# efr32_ioport.net
KiCad netlist of a schematic drawn in Altium Designer
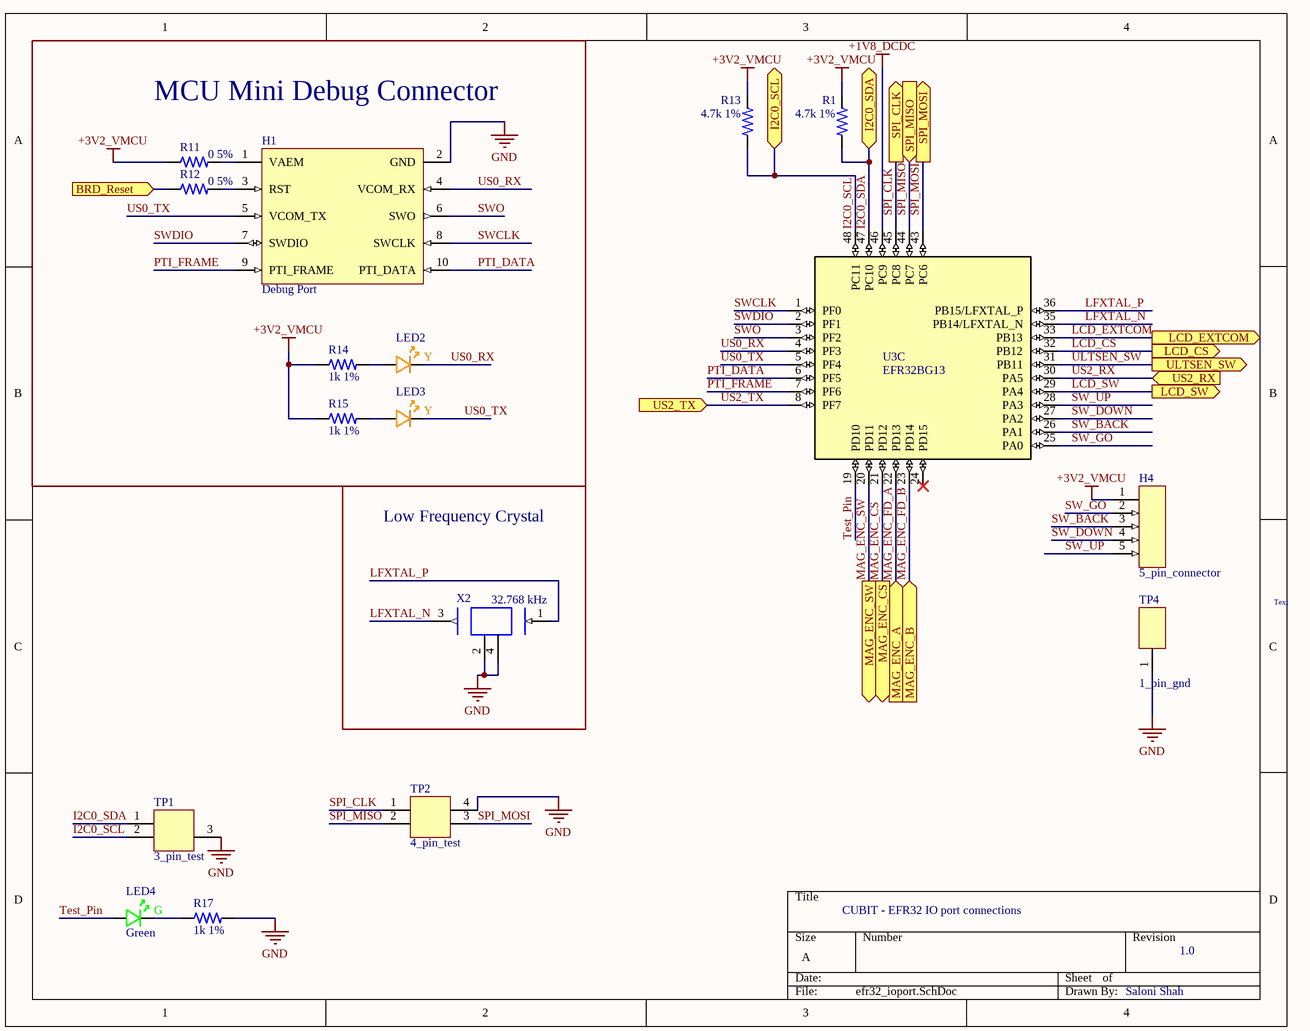
[diagram p0: efr32_ioport.SchDoc]

(export (version "E")
  (design (tool "Eeschema 10.0.6"))
  (components
    (comp (ref "H1")
      (value "Debug Port")
      (footprint "Amphenol_20021121_0")
      (description "CONN HEADER SMD 10POS 1.27MM. Connector Header Surface Mount 10 position 0.050\"")
      (fields
        (field (name "MANUFACTURER") "Amphenol ICC / FCI")
        (field (name "MANUFACTURER PART NUMBER") "20021121-00010C1LF")
      )
      (libsource (lib "LPEDT_proj_lib") (part "20021121-00010C1LF"))
    )
    (comp (ref "H4")
      (value "5_pin_connector")
      (footprint "5_PIN_100MIL")
      (libsource (lib "LPEDT_proj_lib") (part "5_pin_connector"))
    )
    (comp (ref "LED2")
      (value "150060YS75000")
      (footprint "LED_0603_RED_WL-SMCW")
      (description "Led, Yellow, 590 Nm, 2 V, 30 Ma, 120 Mcd Rohs Compliant: Yes")
      (fields (field (name "MANUFACTURER") "Wurth Electronics"))
      (libsource (lib "LPEDT_proj_lib") (part "150060YS75000"))
    )
    (comp (ref "LED3")
      (value "150060YS75000")
      (footprint "LED_0603_RED_WL-SMCW")
      (description "Led, Yellow, 590 Nm, 2 V, 30 Ma, 120 Mcd Rohs Compliant: Yes")
      (fields (field (name "MANUFACTURER") "Wurth Electronics"))
      (libsource (lib "LPEDT_proj_lib") (part "150060YS75000"))
    )
    (comp (ref "LED4")
      (value "Green")
      (footprint "LED_0603_RED_WL-SMCW")
      (description "Led Green Clear 0603 SMD")
      (fields
        (field (name "MANUFACTURER") "QT-Brightek")
        (field (name "MANUFACTURER PART NUMBER") "QBLP601-AG1")
      )
      (libsource (lib "LPEDT_proj_lib") (part "QBLP601-AG1"))
    )
    (comp (ref "R1")
      (value "4.7k 1%")
      (footprint "LPEDT_proj_lib:CAP_0603_1MM")
      (description "Res Thick Film 0603 4.7K Ohm 1% 1/10W ±100ppm/°C Molded SMD Paper T/R")
      (fields
        (field (name "MANUFACTURER") "Yageo")
        (field (name "MANUFACTURER PART NUMBER") "AF0603FR-074K7L")
      )
      (libsource (lib "LPEDT_proj_lib") (part "AF0603FR-074K7L"))
    )
    (comp (ref "R11")
      (value "0 5%")
      (footprint "CAP_0402_1mm")
      (description "Res 0 Ohms ±5% 0.063 W 0402 Thick Film Surface Mount Chip Resistor")
      (fields
        (field (name "MANUFACTURER") "Samsung")
        (field (name "MANUFACTURER PART NUMBER") "RC1005J000CS")
      )
      (libsource (lib "LPEDT_proj_lib") (part "RC1005J000CS"))
    )
    (comp (ref "R12")
      (value "0 5%")
      (footprint "CAP_0402_1mm")
      (description "Res 0 Ohms ±5% 0.063 W 0402 Thick Film Surface Mount Chip Resistor")
      (fields
        (field (name "MANUFACTURER") "Samsung")
        (field (name "MANUFACTURER PART NUMBER") "RC1005J000CS")
      )
      (libsource (lib "LPEDT_proj_lib") (part "RC1005J000CS"))
    )
    (comp (ref "R13")
      (value "4.7k 1%")
      (footprint "LPEDT_proj_lib:CAP_0603_1MM")
      (description "Res Thick Film 0603 4.7K Ohm 1% 1/10W ±100ppm/°C Molded SMD Paper T/R")
      (fields
        (field (name "MANUFACTURER") "Yageo")
        (field (name "MANUFACTURER PART NUMBER") "AF0603FR-074K7L")
      )
      (libsource (lib "LPEDT_proj_lib") (part "AF0603FR-074K7L"))
    )
    (comp (ref "R14")
      (value "1k 1%")
      (footprint "2_Chip_0603_RMCF")
      (description "Res 1K Ohm 1% 0.1W(1/10W) ±100ppm/C Pad SMD Automotive T/R")
      (fields
        (field (name "MANUFACTURER") "Stackpole Electronics")
        (field (name "MANUFACTURER PART NUMBER") "RMCF0603FT1K00")
      )
      (libsource (lib "LPEDT_proj_lib") (part "RMCF0603FT1K00"))
    )
    (comp (ref "R15")
      (value "1k 1%")
      (footprint "2_Chip_0603_RMCF")
      (description "Res 1K Ohm 1% 0.1W(1/10W) ±100ppm/C Pad SMD Automotive T/R")
      (fields
        (field (name "MANUFACTURER") "Stackpole Electronics")
        (field (name "MANUFACTURER PART NUMBER") "RMCF0603FT1K00")
      )
      (libsource (lib "LPEDT_proj_lib") (part "RMCF0603FT1K00"))
    )
    (comp (ref "R17")
      (value "1k 1%")
      (footprint "2_Chip_0603_RMCF")
      (description "Res 1K Ohm 1% 0.1W(1/10W) ±100ppm/C Pad SMD Automotive T/R")
      (fields
        (field (name "MANUFACTURER") "Stackpole Electronics")
        (field (name "MANUFACTURER PART NUMBER") "RMCF0603FT1K00")
      )
      (libsource (lib "LPEDT_proj_lib") (part "RMCF0603FT1K00"))
    )
    (comp (ref "TP1")
      (value "3_pin_test")
      (footprint "3_PIN_100mil")
      (libsource (lib "LPEDT_proj_lib") (part "3_pin_test"))
    )
    (comp (ref "TP2")
      (value "4_pin_test")
      (footprint "4_PIN_100MIL")
      (libsource (lib "LPEDT_proj_lib") (part "4_pin_test"))
    )
    (comp (ref "TP4")
      (value "1_pin_gnd")
      (footprint "1_PIN_100MIL")
      (libsource (lib "LPEDT_proj_lib") (part "1_pin_gnd"))
    )
    (comp (ref "U3")
      (value "EFR32BG13")
      (footprint "48-QFN_7x7")
      (description "Blue Gecko QFN48 2.4 G 19 dB BLE/Proprietary 512 kB 64 kB(RAM) 31GPIO")
      (fields
        (field (name "MANUFACTURER") "Silicon Labs")
        (field (name "MANUFACTURER PART NUMBER") "EFR32BG13P732F512GM48-D")
      )
      (libsource (lib "LPEDT_proj_lib") (part "EFR32BG13P732F512GM48-D"))
    )
    (comp (ref "X2")
      (value "32.768 kHz")
      (footprint "OSC_ASDDV-48.000MHZ-LC-T")
      (description "Oscillator XO 0.032768MHz ±25ppm 15pF CMOS 60% 1.8V 4-Pin SMD T/R")
      (fields
        (field (name "MANUFACTURER") "Abracon")
        (field (name "MANUFACTURER PART NUMBER") "ASDK2-32.768KHZ-LR-T3")
      )
      (libsource (lib "LPEDT_proj_lib") (part "ASDK2-32.768KHZ-LR-T3"))
    )
  )
  (nets
    (net (code "1") (name "+1V8_DCDC") (class "Default")
      (node (ref "U3") (pin "46") (pinfunction "PC9_46") (pintype "bidirectional"))
    )
    (net (code "2") (name "+3V2_VMCU") (class "Default")
      (node (ref "H4") (pin "1") (pintype "power_in"))
      (node (ref "R1") (pin "1") (pinfunction "1_1") (pintype "passive"))
      (node (ref "R11") (pin "1") (pinfunction "1_1") (pintype "passive"))
      (node (ref "R13") (pin "1") (pinfunction "1_1") (pintype "passive"))
      (node (ref "R14") (pin "1") (pinfunction "1_1") (pintype "passive"))
      (node (ref "R15") (pin "1") (pinfunction "1_1") (pintype "passive"))
    )
    (net (code "3") (name "/BRD_Reset") (class "Default")
      (node (ref "R12") (pin "1") (pinfunction "1_1") (pintype "passive"))
    )
    (net (code "4") (name "/I2C0_SCL") (class "Default")
      (node (ref "R13") (pin "2") (pinfunction "2_2") (pintype "passive"))
      (node (ref "TP1") (pin "2") (pintype "passive"))
      (node (ref "U3") (pin "48") (pinfunction "PC11_48") (pintype "bidirectional"))
    )
    (net (code "5") (name "/I2C0_SDA") (class "Default")
      (node (ref "R1") (pin "2") (pinfunction "2_2") (pintype "passive"))
      (node (ref "TP1") (pin "1") (pintype "passive"))
      (node (ref "U3") (pin "47") (pinfunction "PC10_47") (pintype "bidirectional"))
    )
    (net (code "6") (name "/LCD_CS") (class "Default")
      (node (ref "U3") (pin "32") (pinfunction "PB12_32") (pintype "bidirectional"))
    )
    (net (code "7") (name "/LCD_EXTCOM") (class "Default")
      (node (ref "U3") (pin "33") (pinfunction "PB13_33") (pintype "bidirectional"))
    )
    (net (code "8") (name "/LCD_SW") (class "Default")
      (node (ref "U3") (pin "29") (pinfunction "PA4_29") (pintype "bidirectional"))
    )
    (net (code "9") (name "/LFXTAL_N") (class "Default")
      (node (ref "U3") (pin "35") (pinfunction "PB14/LFXTAL_N_35") (pintype "bidirectional"))
      (node (ref "X2") (pin "3") (pintype "output"))
    )
    (net (code "10") (name "/LFXTAL_P") (class "Default")
      (node (ref "U3") (pin "36") (pinfunction "PB15/LFXTAL_P_36") (pintype "bidirectional"))
      (node (ref "X2") (pin "1") (pintype "input"))
    )
    (net (code "11") (name "/MAG_ENC_CS") (class "Default")
      (node (ref "U3") (pin "21") (pinfunction "PD12_21") (pintype "bidirectional"))
    )
    (net (code "12") (name "/MAG_ENC_FD_A") (class "Default")
      (node (ref "U3") (pin "22") (pinfunction "PD13_22") (pintype "bidirectional"))
    )
    (net (code "13") (name "/MAG_ENC_FD_B") (class "Default")
      (node (ref "U3") (pin "23") (pinfunction "PD14_23") (pintype "bidirectional"))
    )
    (net (code "14") (name "/MAG_ENC_SW") (class "Default")
      (node (ref "U3") (pin "20") (pinfunction "PD11_20") (pintype "bidirectional"))
    )
    (net (code "15") (name "/PTI_DATA") (class "Default")
      (node (ref "H1") (pin "10") (pinfunction "PTI_DATA_10") (pintype "input"))
      (node (ref "U3") (pin "6") (pinfunction "PF5_6") (pintype "bidirectional"))
    )
    (net (code "16") (name "/PTI_FRAME") (class "Default")
      (node (ref "H1") (pin "9") (pinfunction "PTI_FRAME_9") (pintype "input"))
      (node (ref "U3") (pin "7") (pinfunction "PF6_7") (pintype "bidirectional"))
    )
    (net (code "17") (name "/SPI_CLK") (class "Default")
      (node (ref "TP2") (pin "1") (pintype "passive"))
      (node (ref "U3") (pin "45") (pinfunction "PC8_45") (pintype "bidirectional"))
    )
    (net (code "18") (name "/SPI_MISO") (class "Default")
      (node (ref "TP2") (pin "2") (pintype "passive"))
      (node (ref "U3") (pin "44") (pinfunction "PC7_44") (pintype "bidirectional"))
    )
    (net (code "19") (name "/SPI_MOSI") (class "Default")
      (node (ref "TP2") (pin "3") (pintype "passive"))
      (node (ref "U3") (pin "43") (pinfunction "PC6_43") (pintype "bidirectional"))
    )
    (net (code "20") (name "/SWCLK") (class "Default")
      (node (ref "H1") (pin "8") (pinfunction "SWCLK_8") (pintype "input"))
      (node (ref "U3") (pin "1") (pinfunction "PF0_1") (pintype "bidirectional"))
    )
    (net (code "21") (name "/SWDIO") (class "Default")
      (node (ref "H1") (pin "7") (pinfunction "SWDIO_7") (pintype "bidirectional"))
      (node (ref "U3") (pin "2") (pinfunction "PF1_2") (pintype "bidirectional"))
    )
    (net (code "22") (name "/SWO") (class "Default")
      (node (ref "H1") (pin "6") (pinfunction "SWO_6") (pintype "output"))
      (node (ref "U3") (pin "3") (pinfunction "PF2_3") (pintype "bidirectional"))
    )
    (net (code "23") (name "/SW_BACK") (class "Default")
      (node (ref "H4") (pin "3") (pintype "input"))
      (node (ref "U3") (pin "26") (pinfunction "PA1_26") (pintype "bidirectional"))
    )
    (net (code "24") (name "/SW_DOWN") (class "Default")
      (node (ref "H4") (pin "4") (pintype "input"))
      (node (ref "U3") (pin "27") (pinfunction "PA2_27") (pintype "bidirectional"))
    )
    (net (code "25") (name "/SW_GO") (class "Default")
      (node (ref "H4") (pin "2") (pintype "input"))
      (node (ref "U3") (pin "25") (pinfunction "PA0_25") (pintype "bidirectional"))
    )
    (net (code "26") (name "/SW_UP") (class "Default")
      (node (ref "H4") (pin "5") (pintype "input"))
      (node (ref "U3") (pin "28") (pinfunction "PA3_28") (pintype "bidirectional"))
    )
    (net (code "27") (name "/Test_Pin") (class "Default")
      (node (ref "LED4") (pin "A") (pinfunction "A_A") (pintype "passive"))
      (node (ref "U3") (pin "19") (pinfunction "PD10_19") (pintype "bidirectional"))
    )
    (net (code "28") (name "/ULTSEN_SW") (class "Default")
      (node (ref "U3") (pin "31") (pinfunction "PB11_31") (pintype "bidirectional"))
    )
    (net (code "29") (name "/US0_RX") (class "Default")
      (node (ref "H1") (pin "4") (pinfunction "VCOM_RX_4") (pintype "input"))
      (node (ref "LED2") (pin "C") (pinfunction "C_C") (pintype "passive"))
      (node (ref "U3") (pin "4") (pinfunction "PF3_4") (pintype "bidirectional"))
    )
    (net (code "30") (name "/US0_TX") (class "Default")
      (node (ref "H1") (pin "5") (pinfunction "VCOM_TX_5") (pintype "input"))
      (node (ref "LED3") (pin "C") (pinfunction "C_C") (pintype "passive"))
      (node (ref "U3") (pin "5") (pinfunction "PF4_5") (pintype "bidirectional"))
    )
    (net (code "31") (name "/US2_RX") (class "Default")
      (node (ref "U3") (pin "30") (pinfunction "PA5_30") (pintype "bidirectional"))
    )
    (net (code "32") (name "/US2_TX") (class "Default")
      (node (ref "U3") (pin "8") (pinfunction "PF7_8") (pintype "bidirectional"))
    )
    (net (code "33") (name "GND") (class "Default")
      (node (ref "H1") (pin "2") (pinfunction "GND_2") (pintype "power_in"))
      (node (ref "R17") (pin "2") (pinfunction "2_2") (pintype "passive"))
      (node (ref "TP1") (pin "3") (pintype "passive"))
      (node (ref "TP2") (pin "4") (pintype "passive"))
      (node (ref "TP4") (pin "1") (pintype "passive"))
      (node (ref "X2") (pin "2") (pintype "power_in"))
      (node (ref "X2") (pin "4") (pintype "power_in"))
    )
    (net (code "34") (name "Net-(H1-RST)") (class "Default")
      (node (ref "H1") (pin "3") (pinfunction "RST_3") (pintype "input"))
      (node (ref "R12") (pin "2") (pinfunction "2_2") (pintype "passive"))
    )
    (net (code "35") (name "Net-(H1-VAEM)") (class "Default")
      (node (ref "H1") (pin "1") (pinfunction "VAEM_1") (pintype "power_in"))
      (node (ref "R11") (pin "2") (pinfunction "2_2") (pintype "passive"))
    )
    (net (code "36") (name "Net-(LED2-PadA)") (class "Default")
      (node (ref "LED2") (pin "A") (pinfunction "A_A") (pintype "passive"))
      (node (ref "R14") (pin "2") (pinfunction "2_2") (pintype "passive"))
    )
    (net (code "37") (name "Net-(LED3-PadA)") (class "Default")
      (node (ref "LED3") (pin "A") (pinfunction "A_A") (pintype "passive"))
      (node (ref "R15") (pin "2") (pinfunction "2_2") (pintype "passive"))
    )
    (net (code "38") (name "Net-(LED4-PadC)") (class "Default")
      (node (ref "LED4") (pin "C") (pinfunction "C_C") (pintype "passive"))
      (node (ref "R17") (pin "1") (pinfunction "1_1") (pintype "passive"))
    )
    (net (code "39") (name "unconnected-(U3C-PD15-Pad24)") (class "Default")
      (node (ref "U3") (pin "24") (pinfunction "PD15_24") (pintype "bidirectional+no_connect"))
    )
  )
)
